# working.net
KiCad netlist of a schematic drawn in EAGLE
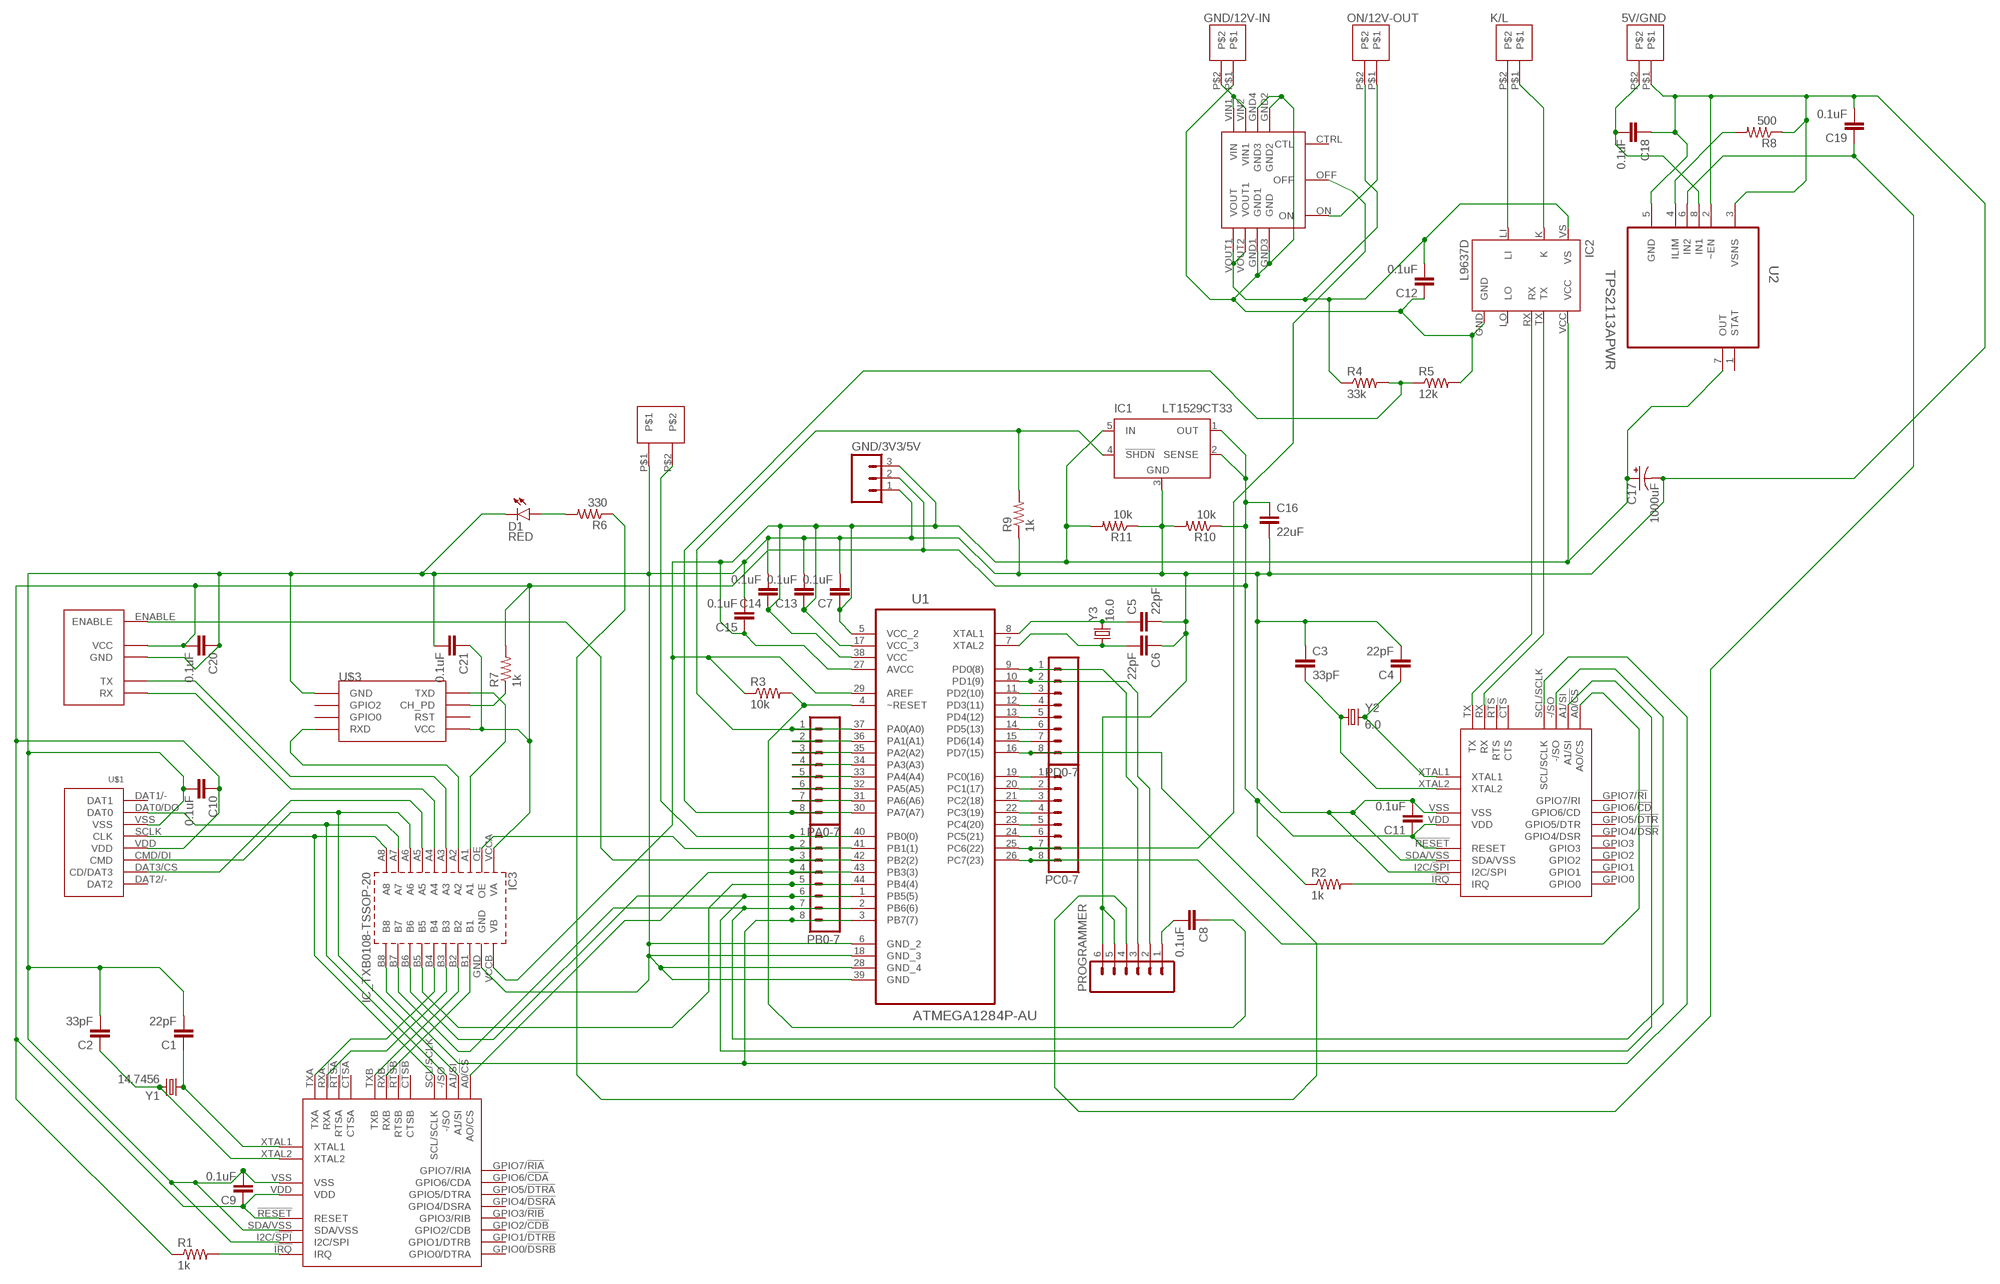
[diagram p0: schematic, sheet 1]

(export (version "E")
  (design (tool "Eeschema 10.0.6"))
  (components
    (comp (ref "5V/GND")
      (value "2-PIN-TERMINAL")
      (footprint "eagle-import:2-PIN-TERMINAL")
      (libsource (lib "eagle-import") (part "2-PIN-TERMINAL"))
    )
    (comp (ref "C1")
      (value "22pF")
      (footprint "eagle-import:0805")
      (libsource (lib "eagle-import") (part "SparkFun-Passives_CAP0805"))
    )
    (comp (ref "C2")
      (value "33pF")
      (footprint "eagle-import:0805")
      (libsource (lib "eagle-import") (part "SparkFun-Passives_CAP0805"))
    )
    (comp (ref "C3")
      (value "33pF")
      (footprint "eagle-import:0805")
      (libsource (lib "eagle-import") (part "SparkFun-Passives_CAP0805"))
    )
    (comp (ref "C4")
      (value "22pF")
      (footprint "eagle-import:0805")
      (libsource (lib "eagle-import") (part "SparkFun-Passives_CAP0805"))
    )
    (comp (ref "C5")
      (value "22pF")
      (footprint "eagle-import:0805")
      (libsource (lib "eagle-import") (part "SparkFun-Passives_CAP0805"))
    )
    (comp (ref "C6")
      (value "22pF")
      (footprint "eagle-import:0805")
      (libsource (lib "eagle-import") (part "SparkFun-Passives_CAP0805"))
    )
    (comp (ref "C7")
      (value "0.1uF")
      (footprint "eagle-import:0603-CAP")
      (libsource (lib "eagle-import") (part "CAP0603-CAP"))
    )
    (comp (ref "C8")
      (value "0.1uF")
      (footprint "eagle-import:0805")
      (libsource (lib "eagle-import") (part "SparkFun-Passives_CAP0805"))
    )
    (comp (ref "C9")
      (value "0.1uF")
      (footprint "eagle-import:0603-CAP")
      (libsource (lib "eagle-import") (part "CAP0603-CAP"))
    )
    (comp (ref "C10")
      (value "0.1uF")
      (footprint "eagle-import:0603-CAP")
      (libsource (lib "eagle-import") (part "CAP0603-CAP"))
    )
    (comp (ref "C11")
      (value "0.1uF")
      (footprint "eagle-import:0603-CAP")
      (libsource (lib "eagle-import") (part "CAP0603-CAP"))
    )
    (comp (ref "C12")
      (value "0.1uF")
      (footprint "eagle-import:0603-CAP")
      (libsource (lib "eagle-import") (part "CAP0603-CAP"))
    )
    (comp (ref "C13")
      (value "0.1uF")
      (footprint "eagle-import:0603-CAP")
      (libsource (lib "eagle-import") (part "CAP0603-CAP"))
    )
    (comp (ref "C14")
      (value "0.1uF")
      (footprint "eagle-import:0603-CAP")
      (libsource (lib "eagle-import") (part "CAP0603-CAP"))
    )
    (comp (ref "C15")
      (value "0.1uF")
      (footprint "eagle-import:0603-CAP")
      (libsource (lib "eagle-import") (part "CAP0603-CAP"))
    )
    (comp (ref "C16")
      (value "22uF")
      (footprint "eagle-import:1206")
      (libsource (lib "eagle-import") (part "CAP1206"))
    )
    (comp (ref "C17")
      (value "1000uF")
      (footprint "eagle-import:PANASONIC_G")
      (libsource (lib "eagle-import") (part "CPOL-USG"))
    )
    (comp (ref "C18")
      (value "0.1uF")
      (footprint "eagle-import:0603-CAP")
      (libsource (lib "eagle-import") (part "CAP0603-CAP"))
    )
    (comp (ref "C19")
      (value "0.1uF")
      (footprint "eagle-import:0603-CAP")
      (libsource (lib "eagle-import") (part "CAP0603-CAP"))
    )
    (comp (ref "C20")
      (value "0.1uF")
      (footprint "eagle-import:0603-CAP")
      (libsource (lib "eagle-import") (part "CAP0603-CAP"))
    )
    (comp (ref "C21")
      (value "0.1uF")
      (footprint "eagle-import:0603-CAP")
      (libsource (lib "eagle-import") (part "CAP0603-CAP"))
    )
    (comp (ref "D1")
      (value "RED")
      (footprint "eagle-import:LED5MM")
      (libsource (lib "eagle-import") (part "LED5MM"))
    )
    (comp (ref "GND/3V3/5V")
      (value "M03PTH")
      (footprint "eagle-import:1X03")
      (libsource (lib "eagle-import") (part "M03PTH"))
    )
    (comp (ref "GND/12V-IN")
      (value "2-PIN-TERMINAL")
      (footprint "eagle-import:2-PIN-TERMINAL")
      (libsource (lib "eagle-import") (part "2-PIN-TERMINAL"))
    )
    (comp (ref "IC1")
      (value "LT1529CT33")
      (footprint "eagle-import:TO220-5")
      (libsource (lib "eagle-import") (part "LT1529T"))
    )
    (comp (ref "IC2")
      (value "L9637D")
      (footprint "eagle-import:SO08")
      (libsource (lib "eagle-import") (part "L9637D"))
    )
    (comp (ref "IC3")
      (value "IC_TXB0108-TSSOP-20")
      (footprint "eagle-import:TSSOP-20")
      (libsource (lib "eagle-import") (part "IC_TXB0108-TSSOP-20"))
    )
    (comp (ref "K/L")
      (value "2-PIN-TERMINAL")
      (footprint "eagle-import:2-PIN-TERMINAL")
      (libsource (lib "eagle-import") (part "2-PIN-TERMINAL"))
    )
    (comp (ref "ON/12V-OUT")
      (value "2-PIN-TERMINAL")
      (footprint "eagle-import:2-PIN-TERMINAL")
      (libsource (lib "eagle-import") (part "2-PIN-TERMINAL"))
    )
    (comp (ref "PA0-7")
      (value "M08")
      (footprint "eagle-import:1X08_ROUND")
      (libsource (lib "eagle-import") (part "M08"))
    )
    (comp (ref "PB0-7")
      (value "M08")
      (footprint "eagle-import:1X08_ROUND")
      (libsource (lib "eagle-import") (part "M08"))
    )
    (comp (ref "PC0-7")
      (value "M08")
      (footprint "eagle-import:1X08_ROUND")
      (libsource (lib "eagle-import") (part "M08"))
    )
    (comp (ref "PD0-7")
      (value "M08")
      (footprint "eagle-import:1X08_ROUND")
      (libsource (lib "eagle-import") (part "M08"))
    )
    (comp (ref "PROGRAMMER")
      (value "M06SILK_FEMALE_PTH")
      (footprint "eagle-import:1X06")
      (libsource (lib "eagle-import") (part "M06SILK_FEMALE_PTH"))
    )
    (comp (ref "R1")
      (value "1k")
      (footprint "eagle-import:0805")
      (libsource (lib "eagle-import") (part "RESISTOR0805-RES"))
    )
    (comp (ref "R2")
      (value "1k")
      (footprint "eagle-import:0805")
      (libsource (lib "eagle-import") (part "RESISTOR0805-RES"))
    )
    (comp (ref "R3")
      (value "10k")
      (footprint "eagle-import:0805")
      (libsource (lib "eagle-import") (part "RESISTOR0805-RES"))
    )
    (comp (ref "R4")
      (value "33k")
      (footprint "eagle-import:0805")
      (libsource (lib "eagle-import") (part "RESISTOR0805-RES"))
    )
    (comp (ref "R5")
      (value "12k")
      (footprint "eagle-import:0805")
      (libsource (lib "eagle-import") (part "RESISTOR0805-RES"))
    )
    (comp (ref "R6")
      (value "330")
      (footprint "eagle-import:0805")
      (libsource (lib "eagle-import") (part "RESISTOR0805-RES"))
    )
    (comp (ref "R7")
      (value "1k")
      (footprint "eagle-import:0805")
      (libsource (lib "eagle-import") (part "RESISTOR0805-RES"))
    )
    (comp (ref "R8")
      (value "500")
      (footprint "eagle-import:0805")
      (libsource (lib "eagle-import") (part "RESISTOR0805-RES"))
    )
    (comp (ref "R9")
      (value "1k")
      (footprint "eagle-import:0805")
      (libsource (lib "eagle-import") (part "RESISTOR0805-RES"))
    )
    (comp (ref "R10")
      (value "10k")
      (footprint "eagle-import:0805")
      (libsource (lib "eagle-import") (part "RESISTOR0805-RES"))
    )
    (comp (ref "R11")
      (value "10k")
      (footprint "eagle-import:0805")
      (libsource (lib "eagle-import") (part "RESISTOR0805-RES"))
    )
    (comp (ref "U$1")
      (value "CON_MICROSDHINGED")
      (footprint "eagle-import:CON_MICROSD_HINGED")
      (libsource (lib "eagle-import") (part "CON_MICROSDHINGED"))
    )
    (comp (ref "U$2")
      (value "SC16IS752IPW")
      (footprint "eagle-import:TSSOP28")
      (libsource (lib "eagle-import") (part "SC16IS752IPW"))
    )
    (comp (ref "U$3")
      (value "ESP01")
      (footprint "eagle-import:ESP01")
      (libsource (lib "eagle-import") (part "ESP01"))
    )
    (comp (ref "U$4")
      (value "MINI")
      (footprint "eagle-import:MINI")
      (libsource (lib "eagle-import") (part "MINI"))
    )
    (comp (ref "U$5")
      (value "FEATHERWING")
      (footprint "eagle-import:FEATHERWING")
      (libsource (lib "eagle-import") (part "FEATHERWING"))
    )
    (comp (ref "U$7")
      (value "SC16IS750IPW")
      (footprint "eagle-import:TSSOP-24")
      (libsource (lib "eagle-import") (part "SC16IS750IPW"))
    )
    (comp (ref "U$11")
      (value "PIEZO")
      (footprint "eagle-import:17MM-PIEZO")
      (libsource (lib "eagle-import") (part "PIEZO"))
    )
    (comp (ref "U1")
      (value "ATMEGA1284P-AU")
      (footprint "eagle-import:QFP80P1200X1200X120-44N")
      (libsource (lib "eagle-import") (part "ATMEGA1284P-AU"))
    )
    (comp (ref "U2")
      (value "TPS2113APWR")
      (footprint "eagle-import:SOP65P640X120-8N")
      (libsource (lib "eagle-import") (part "TPS2113APWR"))
    )
    (comp (ref "Y1")
      (value "14.7456")
      (footprint "eagle-import:HC49US")
      (libsource (lib "eagle-import") (part "CRYSTALHC49US"))
    )
    (comp (ref "Y2")
      (value "6.0")
      (footprint "eagle-import:HC49US")
      (libsource (lib "eagle-import") (part "CRYSTALHC49US"))
    )
    (comp (ref "Y3")
      (value "16.0")
      (footprint "eagle-import:HC49US")
      (libsource (lib "eagle-import") (part "CRYSTALHC49US"))
    )
  )
  (nets
    (net (code "1") (name "Net-(C1-Pad1)") (class "Default")
      (node (ref "C1") (pin "1") (pinfunction "1_1") (pintype "passive"))
      (node (ref "U$2") (pin "XTAL1") (pinfunction "XTAL1_XTAL1") (pintype "bidirectional"))
      (node (ref "Y1") (pin "1") (pinfunction "1_1") (pintype "passive"))
    )
    (net (code "2") (name "Net-(C2-Pad1)") (class "Default")
      (node (ref "C2") (pin "1") (pinfunction "1_1") (pintype "passive"))
      (node (ref "U$2") (pin "XTAL2") (pinfunction "XTAL2_XTAL2") (pintype "bidirectional"))
      (node (ref "Y1") (pin "2") (pinfunction "2_2") (pintype "passive"))
    )
    (net (code "3") (name "Net-(C3-Pad2)") (class "Default")
      (node (ref "C3") (pin "2") (pinfunction "2_2") (pintype "passive"))
      (node (ref "U$7") (pin "XTAL2") (pinfunction "XTAL2_XTAL2") (pintype "bidirectional"))
      (node (ref "Y2") (pin "1") (pinfunction "1_1") (pintype "passive"))
    )
    (net (code "4") (name "Net-(C4-Pad1)") (class "Default")
      (node (ref "C4") (pin "1") (pinfunction "1_1") (pintype "passive"))
      (node (ref "U$7") (pin "XTAL1") (pinfunction "XTAL1_XTAL1") (pintype "bidirectional"))
      (node (ref "Y2") (pin "2") (pinfunction "2_2") (pintype "passive"))
    )
    (net (code "5") (name "Net-(C8-Pad2)") (class "Default")
      (node (ref "C8") (pin "2") (pinfunction "2_2") (pintype "passive"))
      (node (ref "PROGRAMMER") (pin "1") (pinfunction "1_1") (pintype "passive"))
    )
    (net (code "6") (name "Net-(D1-C)") (class "Default")
      (node (ref "5V/GND") (pin "P$1") (pinfunction "P$1_P$1") (pintype "bidirectional"))
      (node (ref "C1") (pin "2") (pinfunction "2_2") (pintype "passive"))
      (node (ref "C10") (pin "2") (pinfunction "2_2") (pintype "passive"))
      (node (ref "C11") (pin "2") (pinfunction "2_2") (pintype "passive"))
      (node (ref "C13") (pin "2") (pinfunction "2_2") (pintype "passive"))
      (node (ref "C14") (pin "2") (pinfunction "2_2") (pintype "passive"))
      (node (ref "C15") (pin "2") (pinfunction "2_2") (pintype "passive"))
      (node (ref "C16") (pin "2") (pinfunction "2_2") (pintype "passive"))
      (node (ref "C17") (pin "-") (pinfunction "-_-") (pintype "passive"))
      (node (ref "C18") (pin "1") (pinfunction "1_1") (pintype "passive"))
      (node (ref "C19") (pin "2") (pinfunction "2_2") (pintype "passive"))
      (node (ref "C2") (pin "2") (pinfunction "2_2") (pintype "passive"))
      (node (ref "C20") (pin "1") (pinfunction "1_1") (pintype "passive"))
      (node (ref "C21") (pin "2") (pinfunction "2_2") (pintype "passive"))
      (node (ref "C3") (pin "1") (pinfunction "1_1") (pintype "passive"))
      (node (ref "C4") (pin "2") (pinfunction "2_2") (pintype "passive"))
      (node (ref "C5") (pin "2") (pinfunction "2_2") (pintype "passive"))
      (node (ref "C6") (pin "1") (pinfunction "1_1") (pintype "passive"))
      (node (ref "C7") (pin "2") (pinfunction "2_2") (pintype "passive"))
      (node (ref "C9") (pin "2") (pinfunction "2_2") (pintype "passive"))
      (node (ref "D1") (pin "K") (pinfunction "C_K") (pintype "passive"))
      (node (ref "GND/3V3/5V") (pin "1") (pinfunction "1_1") (pintype "passive"))
      (node (ref "IC1") (pin "3") (pinfunction "GND_3") (pintype "power_in"))
      (node (ref "IC3") (pin "GND") (pinfunction "GND_GND") (pintype "bidirectional"))
      (node (ref "PROGRAMMER") (pin "5") (pinfunction "5_5") (pintype "passive"))
      (node (ref "PROGRAMMER") (pin "6") (pinfunction "6_6") (pintype "passive"))
      (node (ref "R10") (pin "2") (pinfunction "2_2") (pintype "passive"))
      (node (ref "R11") (pin "1") (pinfunction "1_1") (pintype "passive"))
      (node (ref "R8") (pin "1") (pinfunction "1_1") (pintype "passive"))
      (node (ref "R9") (pin "1") (pinfunction "1_1") (pintype "passive"))
      (node (ref "U$1") (pin "VSS") (pinfunction "VSS_VSS") (pintype "bidirectional"))
      (node (ref "U$11") (pin "P$1") (pinfunction "P$1_P$1") (pintype "bidirectional"))
      (node (ref "U$2") (pin "I2C/!SPI") (pinfunction "I2C/SPI_I2C/!SPI") (pintype "bidirectional"))
      (node (ref "U$2") (pin "SDA/VSS") (pinfunction "SDA/VSS_SDA/VSS") (pintype "bidirectional"))
      (node (ref "U$2") (pin "VSS") (pinfunction "VSS_VSS") (pintype "bidirectional"))
      (node (ref "U$3") (pin "GND") (pinfunction "GND_GND") (pintype "bidirectional"))
      (node (ref "U$5") (pin "GND") (pinfunction "GND_GND") (pintype "bidirectional"))
      (node (ref "U$7") (pin "I2C/!SPI") (pinfunction "I2C/SPI_I2C/!SPI") (pintype "bidirectional"))
      (node (ref "U$7") (pin "SDA/VSS") (pinfunction "SDA/VSS_SDA/VSS") (pintype "bidirectional"))
      (node (ref "U$7") (pin "VSS") (pinfunction "VSS_VSS") (pintype "bidirectional"))
      (node (ref "U1") (pin "18") (pinfunction "GND_3_18") (pintype "passive"))
      (node (ref "U1") (pin "28") (pinfunction "GND_4_28") (pintype "passive"))
      (node (ref "U1") (pin "39") (pinfunction "GND_39") (pintype "passive"))
      (node (ref "U1") (pin "6") (pinfunction "GND_2_6") (pintype "passive"))
      (node (ref "U2") (pin "2") (pinfunction "~{EN}_2") (pintype "input"))
      (node (ref "U2") (pin "3") (pinfunction "VSNS_3") (pintype "power_in"))
      (node (ref "U2") (pin "5") (pinfunction "GND_5") (pintype "passive"))
    )
    (net (code "7") (name "Net-(D1-PadA)") (class "Default")
      (node (ref "D1") (pin "A") (pinfunction "A_A") (pintype "passive"))
      (node (ref "R6") (pin "2") (pinfunction "2_2") (pintype "passive"))
    )
    (net (code "8") (name "Net-(IC1-IN)") (class "Default")
      (node (ref "C13") (pin "1") (pinfunction "1_1") (pintype "passive"))
      (node (ref "C14") (pin "1") (pinfunction "1_1") (pintype "passive"))
      (node (ref "C15") (pin "1") (pinfunction "1_1") (pintype "passive"))
      (node (ref "C17") (pin "+") (pinfunction "+_+") (pintype "passive"))
      (node (ref "C7") (pin "1") (pinfunction "1_1") (pintype "passive"))
      (node (ref "GND/3V3/5V") (pin "3") (pinfunction "3_3") (pintype "passive"))
      (node (ref "IC1") (pin "5") (pinfunction "IN_5") (pintype "input"))
      (node (ref "IC2") (pin "VCC") (pinfunction "VCC_VCC") (pintype "power_in"))
      (node (ref "IC3") (pin "VCCB") (pinfunction "VB_VCCB") (pintype "bidirectional"))
      (node (ref "R11") (pin "2") (pinfunction "2_2") (pintype "passive"))
      (node (ref "R3") (pin "1") (pinfunction "1_1") (pintype "passive"))
      (node (ref "U1") (pin "17") (pinfunction "VCC_3_17") (pintype "power_in"))
      (node (ref "U1") (pin "27") (pinfunction "AVCC_27") (pintype "power_in"))
      (node (ref "U1") (pin "29") (pinfunction "AREF_29") (pintype "input"))
      (node (ref "U1") (pin "38") (pinfunction "VCC_38") (pintype "power_in"))
      (node (ref "U1") (pin "5") (pinfunction "VCC_2_5") (pintype "power_in"))
      (node (ref "U2") (pin "7") (pinfunction "OUT_7") (pintype "output"))
    )
    (net (code "9") (name "Net-(IC1-OUT)") (class "Default")
      (node (ref "C10") (pin "1") (pinfunction "1_1") (pintype "passive"))
      (node (ref "C11") (pin "1") (pinfunction "1_1") (pintype "passive"))
      (node (ref "C16") (pin "1") (pinfunction "1_1") (pintype "passive"))
      (node (ref "C20") (pin "2") (pinfunction "2_2") (pintype "passive"))
      (node (ref "C21") (pin "1") (pinfunction "1_1") (pintype "passive"))
      (node (ref "C9") (pin "1") (pinfunction "1_1") (pintype "passive"))
      (node (ref "GND/3V3/5V") (pin "2") (pinfunction "2_2") (pintype "passive"))
      (node (ref "IC1") (pin "1") (pinfunction "OUT_1") (pintype "output"))
      (node (ref "IC1") (pin "2") (pinfunction "SENSE_2") (pintype "input"))
      (node (ref "IC3") (pin "VCCA") (pinfunction "VA_VCCA") (pintype "bidirectional"))
      (node (ref "R1") (pin "1") (pinfunction "1_1") (pintype "passive"))
      (node (ref "R10") (pin "1") (pinfunction "1_1") (pintype "passive"))
      (node (ref "R2") (pin "1") (pinfunction "1_1") (pintype "passive"))
      (node (ref "R7") (pin "2") (pinfunction "2_2") (pintype "passive"))
      (node (ref "U$1") (pin "VDD") (pinfunction "VDD_VDD") (pintype "bidirectional"))
      (node (ref "U$2") (pin "!RESET") (pinfunction "RESET_!RESET") (pintype "bidirectional"))
      (node (ref "U$2") (pin "VDD") (pinfunction "VDD_VDD") (pintype "bidirectional"))
      (node (ref "U$3") (pin "VCC") (pinfunction "VCC_VCC") (pintype "bidirectional"))
      (node (ref "U$5") (pin "VCC") (pinfunction "VCC_VCC") (pintype "bidirectional"))
      (node (ref "U$7") (pin "!RESET") (pinfunction "RESET_!RESET") (pintype "bidirectional"))
      (node (ref "U$7") (pin "VDD") (pinfunction "VDD_VDD") (pintype "bidirectional"))
    )
    (net (code "10") (name "Net-(IC1-~{SHDN})") (class "Default")
      (node (ref "IC1") (pin "4") (pinfunction "~{SHDN}_4") (pintype "input"))
      (node (ref "PA0-7") (pin "1") (pinfunction "1_1") (pintype "passive"))
      (node (ref "R9") (pin "2") (pinfunction "2_2") (pintype "passive"))
      (node (ref "U1") (pin "37") (pinfunction "PA0(A0)_37") (pintype "bidirectional"))
    )
    (net (code "11") (name "Net-(IC2-PadK)") (class "Default")
      (node (ref "IC2") (pin "K") (pinfunction "K_K") (pintype "input"))
      (node (ref "K/L") (pin "P$1") (pinfunction "P$1_P$1") (pintype "bidirectional"))
    )
    (net (code "12") (name "Net-(IC2-PadLI)") (class "Default")
      (node (ref "IC2") (pin "LI") (pinfunction "LI_LI") (pintype "input"))
      (node (ref "K/L") (pin "P$2") (pinfunction "P$2_P$2") (pintype "bidirectional"))
    )
    (net (code "13") (name "Net-(IC2-PadRX)") (class "Default")
      (node (ref "IC2") (pin "RX") (pinfunction "RX_RX") (pintype "output"))
      (node (ref "U$7") (pin "TX") (pinfunction "TX_TX") (pintype "bidirectional"))
    )
    (net (code "14") (name "Net-(IC2-PadTX)") (class "Default")
      (node (ref "IC2") (pin "TX") (pinfunction "TX_TX") (pintype "input"))
      (node (ref "U$7") (pin "RX") (pinfunction "RX_RX") (pintype "bidirectional"))
    )
    (net (code "15") (name "Net-(IC3-PadB1)") (class "Default")
      (node (ref "IC3") (pin "B1") (pinfunction "B1_B1") (pintype "bidirectional"))
      (node (ref "U$2") (pin "RXB") (pinfunction "RXB_RXB") (pintype "bidirectional"))
    )
    (net (code "16") (name "Net-(IC3-PadB2)") (class "Default")
      (node (ref "IC3") (pin "B2") (pinfunction "B2_B2") (pintype "bidirectional"))
      (node (ref "U$2") (pin "TXB") (pinfunction "TXB_TXB") (pintype "bidirectional"))
    )
    (net (code "17") (name "Net-(IC3-PadB3)") (class "Default")
      (node (ref "IC3") (pin "B3") (pinfunction "B3_B3") (pintype "bidirectional"))
      (node (ref "U$2") (pin "RXA") (pinfunction "RXA_RXA") (pintype "bidirectional"))
    )
    (net (code "18") (name "Net-(IC3-PadB4)") (class "Default")
      (node (ref "IC3") (pin "B4") (pinfunction "B4_B4") (pintype "bidirectional"))
      (node (ref "U$2") (pin "TXA") (pinfunction "TXA_TXA") (pintype "bidirectional"))
    )
    (net (code "19") (name "Net-(ON/12V-OUT-PadP$1)") (class "Default")
      (node (ref "ON/12V-OUT") (pin "P$1") (pinfunction "P$1_P$1") (pintype "bidirectional"))
      (node (ref "U$4") (pin "ON") (pinfunction "ON_ON") (pintype "bidirectional"))
    )
    (net (code "20") (name "Net-(R7-Pad1)") (class "Default")
      (node (ref "R7") (pin "1") (pinfunction "1_1") (pintype "passive"))
      (node (ref "U$3") (pin "CH_PD") (pinfunction "CH_PD_CH_PD") (pintype "bidirectional"))
    )
    (net (code "21") (name "Net-(U$1-CD{slash}DAT3)") (class "Default")
      (node (ref "IC3") (pin "A5") (pinfunction "A5_A5") (pintype "bidirectional"))
      (node (ref "U$1") (pin "DAT3/CS") (pinfunction "CD/DAT3_DAT3/CS") (pintype "bidirectional"))
    )
    (net (code "22") (name "Net-(U$1-CLK)") (class "Default")
      (node (ref "IC3") (pin "A8") (pinfunction "A8_A8") (pintype "bidirectional"))
      (node (ref "U$1") (pin "SCLK") (pinfunction "CLK_SCLK") (pintype "bidirectional"))
      (node (ref "U$2") (pin "SCL/SCLK") (pinfunction "SCL/SCLK_SCL/SCLK") (pintype "bidirectional"))
    )
    (net (code "23") (name "Net-(U$1-CMD)") (class "Default")
      (node (ref "IC3") (pin "A6") (pinfunction "A6_A6") (pintype "bidirectional"))
      (node (ref "U$1") (pin "CMD/DI") (pinfunction "CMD_CMD/DI") (pintype "bidirectional"))
      (node (ref "U$2") (pin "A1/SI") (pinfunction "A1/SI_A1/SI") (pintype "bidirectional"))
    )
    (net (code "24") (name "Net-(U$1-DAT0)") (class "Default")
      (node (ref "IC3") (pin "A7") (pinfunction "A7_A7") (pintype "bidirectional"))
      (node (ref "U$1") (pin "DAT0/DO") (pinfunction "DAT0_DAT0/DO") (pintype "bidirectional"))
      (node (ref "U$2") (pin "-/SO") (pinfunction "-/SO_-/SO") (pintype "bidirectional"))
    )
    (net (code "25") (name "Net-(U$2-AO{slash}CS)") (class "Default")
      (node (ref "PB0-7") (pin "4") (pinfunction "4_4") (pintype "passive"))
      (node (ref "U$2") (pin "A0/!CS") (pinfunction "AO/CS_A0/!CS") (pintype "bidirectional"))
      (node (ref "U1") (pin "43") (pinfunction "PB3(3)_43") (pintype "bidirectional"))
    )
    (net (code "26") (name "Net-(U$2-IRQ)") (class "Default")
      (node (ref "R1") (pin "2") (pinfunction "2_2") (pintype "passive"))
      (node (ref "U$2") (pin "!IRQ") (pinfunction "IRQ_!IRQ") (pintype "bidirectional"))
    )
    (net (code "27") (name "Net-(U$3-RXD)") (class "Default")
      (node (ref "IC3") (pin "A2") (pinfunction "A2_A2") (pintype "bidirectional"))
      (node (ref "U$3") (pin "RX") (pinfunction "RXD_RX") (pintype "bidirectional"))
    )
    (net (code "28") (name "Net-(U$3-TXD)") (class "Default")
      (node (ref "IC3") (pin "A1") (pinfunction "A1_A1") (pintype "bidirectional"))
      (node (ref "U$3") (pin "TX") (pinfunction "TXD_TX") (pintype "bidirectional"))
    )
    (net (code "29") (name "Net-(U$4-GND)") (class "Default")
      (node (ref "C12") (pin "1") (pinfunction "1_1") (pintype "passive"))
      (node (ref "GND/12V-IN") (pin "P$1") (pinfunction "P$1_P$1") (pintype "bidirectional"))
      (node (ref "IC2") (pin "GND") (pinfunction "GND_GND") (pintype "power_in"))
      (node (ref "R5") (pin "2") (pinfunction "2_2") (pintype "passive"))
      (node (ref "U$4") (pin "GND1") (pinfunction "GND1_GND1") (pintype "bidirectional"))
      (node (ref "U$4") (pin "GND2") (pinfunction "GND2_GND2") (pintype "bidirectional"))
      (node (ref "U$4") (pin "GND3") (pinfunction "GND_GND3") (pintype "bidirectional"))
      (node (ref "U$4") (pin "GND4") (pinfunction "GND3_GND4") (pintype "bidirectional"))
    )
    (net (code "30") (name "Net-(U$4-VIN)") (class "Default")
      (node (ref "GND/12V-IN") (pin "P$2") (pinfunction "P$2_P$2") (pintype "bidirectional"))
      (node (ref "U$4") (pin "VIN1") (pinfunction "VIN_VIN1") (pintype "bidirectional"))
      (node (ref "U$4") (pin "VIN2") (pinfunction "VIN1_VIN2") (pintype "bidirectional"))
    )
    (net (code "31") (name "Net-(U$4-VOUT)") (class "Default")
      (node (ref "C12") (pin "2") (pinfunction "2_2") (pintype "passive"))
      (node (ref "IC2") (pin "VS") (pinfunction "VS_VS") (pintype "power_in"))
      (node (ref "ON/12V-OUT") (pin "P$2") (pinfunction "P$2_P$2") (pintype "bidirectional"))
      (node (ref "R4") (pin "1") (pinfunction "1_1") (pintype "passive"))
      (node (ref "U$4") (pin "VOUT1") (pinfunction "VOUT_VOUT1") (pintype "bidirectional"))
      (node (ref "U$4") (pin "VOUT2") (pinfunction "VOUT1_VOUT2") (pintype "bidirectional"))
    )
    (net (code "32") (name "Net-(U$5-RX)") (class "Default")
      (node (ref "IC3") (pin "A4") (pinfunction "A4_A4") (pintype "bidirectional"))
      (node (ref "U$5") (pin "RX-2") (pinfunction "RX_RX-2") (pintype "bidirectional"))
    )
    (net (code "33") (name "Net-(U$5-TX)") (class "Default")
      (node (ref "IC3") (pin "A3") (pinfunction "A3_A3") (pintype "bidirectional"))
      (node (ref "U$5") (pin "TX-2") (pinfunction "TX_TX-2") (pintype "bidirectional"))
    )
    (net (code "34") (name "Net-(U$7-AO{slash}CS)") (class "Default")
      (node (ref "PC0-7") (pin "8") (pinfunction "8_8") (pintype "passive"))
      (node (ref "U$7") (pin "A0/!CS") (pinfunction "AO/CS_A0/!CS") (pintype "bidirectional"))
      (node (ref "U1") (pin "26") (pinfunction "PC7(23)_26") (pintype "bidirectional"))
    )
    (net (code "35") (name "Net-(U$7-IRQ)") (class "Default")
      (node (ref "R2") (pin "2") (pinfunction "2_2") (pintype "passive"))
      (node (ref "U$7") (pin "!IRQ") (pinfunction "IRQ_!IRQ") (pintype "bidirectional"))
    )
    (net (code "36") (name "Net-(U1-PA1(A1))") (class "Default")
      (node (ref "PA0-7") (pin "2") (pinfunction "2_2") (pintype "passive"))
      (node (ref "U1") (pin "36") (pinfunction "PA1(A1)_36") (pintype "bidirectional"))
    )
    (net (code "37") (name "Net-(U1-PA2(A2))") (class "Default")
      (node (ref "PA0-7") (pin "3") (pinfunction "3_3") (pintype "passive"))
      (node (ref "U1") (pin "35") (pinfunction "PA2(A2)_35") (pintype "bidirectional"))
    )
    (net (code "38") (name "Net-(U1-PA3(A3))") (class "Default")
      (node (ref "PA0-7") (pin "4") (pinfunction "4_4") (pintype "passive"))
      (node (ref "U1") (pin "34") (pinfunction "PA3(A3)_34") (pintype "bidirectional"))
    )
    (net (code "39") (name "Net-(U1-PA4(A4))") (class "Default")
      (node (ref "PA0-7") (pin "5") (pinfunction "5_5") (pintype "passive"))
      (node (ref "U1") (pin "33") (pinfunction "PA4(A4)_33") (pintype "bidirectional"))
    )
    (net (code "40") (name "Net-(U1-PA5(A5))") (class "Default")
      (node (ref "PA0-7") (pin "6") (pinfunction "6_6") (pintype "passive"))
      (node (ref "U1") (pin "32") (pinfunction "PA5(A5)_32") (pintype "bidirectional"))
    )
    (net (code "41") (name "Net-(U1-PA6(A6))") (class "Default")
      (node (ref "PA0-7") (pin "7") (pinfunction "7_7") (pintype "passive"))
      (node (ref "U1") (pin "31") (pinfunction "PA6(A6)_31") (pintype "bidirectional"))
    )
    (net (code "42") (name "Net-(U1-PA7(A7))") (class "Default")
      (node (ref "PA0-7") (pin "8") (pinfunction "8_8") (pintype "passive"))
      (node (ref "R4") (pin "2") (pinfunction "2_2") (pintype "passive"))
      (node (ref "R5") (pin "1") (pinfunction "1_1") (pintype "passive"))
      (node (ref "U1") (pin "30") (pinfunction "PA7(A7)_30") (pintype "bidirectional"))
    )
    (net (code "43") (name "Net-(U1-PB0(0))") (class "Default")
      (node (ref "PB0-7") (pin "1") (pinfunction "1_1") (pintype "passive"))
      (node (ref "U$11") (pin "P$2") (pinfunction "P$2_P$2") (pintype "bidirectional"))
      (node (ref "U1") (pin "40") (pinfunction "PB0(0)_40") (pintype "bidirectional"))
    )
    (net (code "44") (name "Net-(U1-PB1(1))") (class "Default")
      (node (ref "IC3") (pin "OE") (pinfunction "OE_OE") (pintype "bidirectional"))
      (node (ref "PB0-7") (pin "2") (pinfunction "2_2") (pintype "passive"))
      (node (ref "U1") (pin "41") (pinfunction "PB1(1)_41") (pintype "bidirectional"))
    )
    (net (code "45") (name "Net-(U1-PB2(2))") (class "Default")
      (node (ref "PB0-7") (pin "3") (pinfunction "3_3") (pintype "passive"))
      (node (ref "U$5") (pin "ENABLE") (pinfunction "ENABLE_ENABLE") (pintype "bidirectional"))
      (node (ref "U1") (pin "42") (pinfunction "PB2(2)_42") (pintype "bidirectional"))
    )
    (net (code "46") (name "Net-(U1-PB4(4))") (class "Default")
      (node (ref "IC3") (pin "B5") (pinfunction "B5_B5") (pintype "bidirectional"))
      (node (ref "PB0-7") (pin "5") (pinfunction "5_5") (pintype "passive"))
      (node (ref "U1") (pin "44") (pinfunction "PB4(4)_44") (pintype "bidirectional"))
    )
    (net (code "47") (name "Net-(U1-PB5(5))") (class "Default")
      (node (ref "IC3") (pin "B6") (pinfunction "B6_B6") (pintype "bidirectional"))
      (node (ref "PB0-7") (pin "6") (pinfunction "6_6") (pintype "passive"))
      (node (ref "U$7") (pin "A1/SI") (pinfunction "A1/SI_A1/SI") (pintype "bidirectional"))
      (node (ref "U1") (pin "1") (pinfunction "PB5(5)_1") (pintype "bidirectional"))
    )
    (net (code "48") (name "Net-(U1-PB6(6))") (class "Default")
      (node (ref "IC3") (pin "B7") (pinfunction "B7_B7") (pintype "bidirectional"))
      (node (ref "PB0-7") (pin "7") (pinfunction "7_7") (pintype "passive"))
      (node (ref "U$7") (pin "-/SO") (pinfunction "-/SO_-/SO") (pintype "bidirectional"))
      (node (ref "U1") (pin "2") (pinfunction "PB6(6)_2") (pintype "bidirectional"))
    )
    (net (code "49") (name "Net-(U1-PB7(7))") (class "Default")
      (node (ref "IC3") (pin "B8") (pinfunction "B8_B8") (pintype "bidirectional"))
      (node (ref "PB0-7") (pin "8") (pinfunction "8_8") (pintype "passive"))
      (node (ref "U$7") (pin "SCL/SCLK") (pinfunction "SCL/SCLK_SCL/SCLK") (pintype "bidirectional"))
      (node (ref "U1") (pin "3") (pinfunction "PB7(7)_3") (pintype "bidirectional"))
    )
    (net (code "50") (name "Net-(U1-PC0(16))") (class "Default")
      (node (ref "PC0-7") (pin "1") (pinfunction "1_1") (pintype "passive"))
      (node (ref "U1") (pin "19") (pinfunction "PC0(16)_19") (pintype "bidirectional"))
    )
    (net (code "51") (name "Net-(U1-PC1(17))") (class "Default")
      (node (ref "PC0-7") (pin "2") (pinfunction "2_2") (pintype "passive"))
      (node (ref "U1") (pin "20") (pinfunction "PC1(17)_20") (pintype "bidirectional"))
    )
    (net (code "52") (name "Net-(U1-PC2(18))") (class "Default")
      (node (ref "PC0-7") (pin "3") (pinfunction "3_3") (pintype "passive"))
      (node (ref "U1") (pin "21") (pinfunction "PC2(18)_21") (pintype "bidirectional"))
    )
    (net (code "53") (name "Net-(U1-PC3(19))") (class "Default")
      (node (ref "PC0-7") (pin "4") (pinfunction "4_4") (pintype "passive"))
      (node (ref "U1") (pin "22") (pinfunction "PC3(19)_22") (pintype "bidirectional"))
    )
    (net (code "54") (name "Net-(U1-PC4(20))") (class "Default")
      (node (ref "PC0-7") (pin "5") (pinfunction "5_5") (pintype "passive"))
      (node (ref "U1") (pin "23") (pinfunction "PC4(20)_23") (pintype "bidirectional"))
    )
    (net (code "55") (name "Net-(U1-PC5(21))") (class "Default")
      (node (ref "PC0-7") (pin "6") (pinfunction "6_6") (pintype "passive"))
      (node (ref "U1") (pin "24") (pinfunction "PC5(21)_24") (pintype "bidirectional"))
    )
    (net (code "56") (name "Net-(U1-PC6(22))") (class "Default")
      (node (ref "PC0-7") (pin "7") (pinfunction "7_7") (pintype "passive"))
      (node (ref "U$4") (pin "OFF") (pinfunction "OFF_OFF") (pintype "bidirectional"))
      (node (ref "U1") (pin "25") (pinfunction "PC6(22)_25") (pintype "bidirectional"))
    )
    (net (code "57") (name "Net-(U1-PD0(8))") (class "Default")
      (node (ref "PD0-7") (pin "1") (pinfunction "1_1") (pintype "passive"))
      (node (ref "PROGRAMMER") (pin "3") (pinfunction "3_3") (pintype "passive"))
      (node (ref "U1") (pin "9") (pinfunction "PD0(8)_9") (pintype "bidirectional"))
    )
    (net (code "58") (name "Net-(U1-PD1(9))") (class "Default")
      (node (ref "PD0-7") (pin "2") (pinfunction "2_2") (pintype "passive"))
      (node (ref "PROGRAMMER") (pin "2") (pinfunction "2_2") (pintype "passive"))
      (node (ref "U1") (pin "10") (pinfunction "PD1(9)_10") (pintype "bidirectional"))
    )
    (net (code "59") (name "Net-(U1-PD2(10))") (class "Default")
      (node (ref "PD0-7") (pin "3") (pinfunction "3_3") (pintype "passive"))
      (node (ref "U1") (pin "11") (pinfunction "PD2(10)_11") (pintype "bidirectional"))
    )
    (net (code "60") (name "Net-(U1-PD3(11))") (class "Default")
      (node (ref "PD0-7") (pin "4") (pinfunction "4_4") (pintype "passive"))
      (node (ref "U1") (pin "12") (pinfunction "PD3(11)_12") (pintype "bidirectional"))
    )
    (net (code "61") (name "Net-(U1-PD4(12))") (class "Default")
      (node (ref "PD0-7") (pin "5") (pinfunction "5_5") (pintype "passive"))
      (node (ref "U1") (pin "13") (pinfunction "PD4(12)_13") (pintype "bidirectional"))
    )
    (net (code "62") (name "Net-(U1-PD5(13))") (class "Default")
      (node (ref "PD0-7") (pin "6") (pinfunction "6_6") (pintype "passive"))
      (node (ref "U1") (pin "14") (pinfunction "PD5(13)_14") (pintype "bidirectional"))
    )
    (net (code "63") (name "Net-(U1-PD6(14))") (class "Default")
      (node (ref "PD0-7") (pin "7") (pinfunction "7_7") (pintype "passive"))
      (node (ref "U1") (pin "15") (pinfunction "PD6(14)_15") (pintype "bidirectional"))
    )
    (net (code "64") (name "Net-(U1-PD7(15))") (class "Default")
      (node (ref "PD0-7") (pin "8") (pinfunction "8_8") (pintype "passive"))
      (node (ref "R6") (pin "1") (pinfunction "1_1") (pintype "passive"))
      (node (ref "U1") (pin "16") (pinfunction "PD7(15)_16") (pintype "bidirectional"))
    )
    (net (code "65") (name "Net-(U1-XTAL1)") (class "Default")
      (node (ref "C5") (pin "1") (pinfunction "1_1") (pintype "passive"))
      (node (ref "U1") (pin "8") (pinfunction "XTAL1_8") (pintype "input"))
      (node (ref "Y3") (pin "2") (pinfunction "2_2") (pintype "passive"))
    )
    (net (code "66") (name "Net-(U1-XTAL2)") (class "Default")
      (node (ref "C6") (pin "2") (pinfunction "2_2") (pintype "passive"))
      (node (ref "U1") (pin "7") (pinfunction "XTAL2_7") (pintype "output"))
      (node (ref "Y3") (pin "1") (pinfunction "1_1") (pintype "passive"))
    )
    (net (code "67") (name "Net-(U1-~{RESET})") (class "Default")
      (node (ref "C8") (pin "1") (pinfunction "1_1") (pintype "passive"))
      (node (ref "R3") (pin "2") (pinfunction "2_2") (pintype "passive"))
      (node (ref "U1") (pin "4") (pinfunction "~{RESET}_4") (pintype "input"))
    )
    (net (code "68") (name "Net-(U2-ILIM)") (class "Default")
      (node (ref "R8") (pin "2") (pinfunction "2_2") (pintype "passive"))
      (node (ref "U2") (pin "4") (pinfunction "ILIM_4") (pintype "input"))
    )
    (net (code "69") (name "Net-(U2-IN1)") (class "Default")
      (node (ref "5V/GND") (pin "P$2") (pinfunction "P$2_P$2") (pintype "bidirectional"))
      (node (ref "C18") (pin "2") (pinfunction "2_2") (pintype "passive"))
      (node (ref "U2") (pin "8") (pinfunction "IN1_8") (pintype "input"))
    )
    (net (code "70") (name "Net-(U2-IN2)") (class "Default")
      (node (ref "C19") (pin "1") (pinfunction "1_1") (pintype "passive"))
      (node (ref "PROGRAMMER") (pin "4") (pinfunction "4_4") (pintype "passive"))
      (node (ref "U2") (pin "6") (pinfunction "IN2_6") (pintype "input"))
    )
    (net (code "71") (name "unconnected-(IC2-PadLO)") (class "Default")
      (node (ref "IC2") (pin "LO") (pinfunction "LO_LO") (pintype "output"))
    )
    (net (code "72") (name "unconnected-(U$1-DAT1-PadDAT1{slash}-)") (class "Default")
      (node (ref "U$1") (pin "DAT1/-") (pinfunction "DAT1_DAT1/-") (pintype "bidirectional"))
    )
    (net (code "73") (name "unconnected-(U$1-DAT2-PadDAT2{slash}-)") (class "Default")
      (node (ref "U$1") (pin "DAT2/-") (pinfunction "DAT2_DAT2/-") (pintype "bidirectional"))
    )
    (net (code "74") (name "unconnected-(U$2-CTSA-Pad!CTSA)") (class "Default")
      (node (ref "U$2") (pin "!CTSA") (pinfunction "CTSA_!CTSA") (pintype "bidirectional"))
    )
    (net (code "75") (name "unconnected-(U$2-CTSB-Pad!CTSB)") (class "Default")
      (node (ref "U$2") (pin "!CTSB") (pinfunction "CTSB_!CTSB") (pintype "bidirectional"))
    )
    (net (code "76") (name "unconnected-(U$2-GPIO0{slash}DTRA-PadGPIO0{slash}!DSRB)") (class "Default")
      (node (ref "U$2") (pin "GPIO0/!DSRB") (pinfunction "GPIO0/DTRA_GPIO0/!DSRB") (pintype "bidirectional"))
    )
    (net (code "77") (name "unconnected-(U$2-GPIO1{slash}DTRB-PadGPIO1{slash}!DTRB)") (class "Default")
      (node (ref "U$2") (pin "GPIO1/!DTRB") (pinfunction "GPIO1/DTRB_GPIO1/!DTRB") (pintype "bidirectional"))
    )
    (net (code "78") (name "unconnected-(U$2-GPIO2{slash}CDB-PadGPIO2{slash}!CDB)") (class "Default")
      (node (ref "U$2") (pin "GPIO2/!CDB") (pinfunction "GPIO2/CDB_GPIO2/!CDB") (pintype "bidirectional"))
    )
    (net (code "79") (name "unconnected-(U$2-GPIO3{slash}RIB-PadGPIO3{slash}!RIB)") (class "Default")
      (node (ref "U$2") (pin "GPIO3/!RIB") (pinfunction "GPIO3/RIB_GPIO3/!RIB") (pintype "bidirectional"))
    )
    (net (code "80") (name "unconnected-(U$2-GPIO4{slash}DSRA-PadGPIO4{slash}!DSRA)") (class "Default")
      (node (ref "U$2") (pin "GPIO4/!DSRA") (pinfunction "GPIO4/DSRA_GPIO4/!DSRA") (pintype "bidirectional"))
    )
    (net (code "81") (name "unconnected-(U$2-GPIO5{slash}DTRA-PadGPIO5{slash}!DTRA)") (class "Default")
      (node (ref "U$2") (pin "GPIO5/!DTRA") (pinfunction "GPIO5/DTRA_GPIO5/!DTRA") (pintype "bidirectional"))
    )
    (net (code "82") (name "unconnected-(U$2-GPIO6{slash}CDA-PadGPIO6{slash}!CDA)") (class "Default")
      (node (ref "U$2") (pin "GPIO6/!CDA") (pinfunction "GPIO6/CDA_GPIO6/!CDA") (pintype "bidirectional"))
    )
    (net (code "83") (name "unconnected-(U$2-GPIO7{slash}RIA-PadGPIO7{slash}!RIA)") (class "Default")
      (node (ref "U$2") (pin "GPIO7/!RIA") (pinfunction "GPIO7/RIA_GPIO7/!RIA") (pintype "bidirectional"))
    )
    (net (code "84") (name "unconnected-(U$2-RTSA-Pad!RTSA)") (class "Default")
      (node (ref "U$2") (pin "!RTSA") (pinfunction "RTSA_!RTSA") (pintype "bidirectional"))
    )
    (net (code "85") (name "unconnected-(U$2-RTSB-Pad!RTSB)") (class "Default")
      (node (ref "U$2") (pin "!RTSB") (pinfunction "RTSB_!RTSB") (pintype "bidirectional"))
    )
    (net (code "86") (name "unconnected-(U$3-PadGPIO0)") (class "Default")
      (node (ref "U$3") (pin "GPIO0") (pinfunction "GPIO0_GPIO0") (pintype "bidirectional"))
    )
    (net (code "87") (name "unconnected-(U$3-PadGPIO2)") (class "Default")
      (node (ref "U$3") (pin "GPIO2") (pinfunction "GPIO2_GPIO2") (pintype "bidirectional"))
    )
    (net (code "88") (name "unconnected-(U$3-PadRST)") (class "Default")
      (node (ref "U$3") (pin "RST") (pinfunction "RST_RST") (pintype "bidirectional"))
    )
    (net (code "89") (name "unconnected-(U$4-CTL-PadCTRL)") (class "Default")
      (node (ref "U$4") (pin "CTRL") (pinfunction "CTL_CTRL") (pintype "bidirectional"))
    )
    (net (code "90") (name "unconnected-(U$7-CTS-Pad!CTS)") (class "Default")
      (node (ref "U$7") (pin "!CTS") (pinfunction "CTS_!CTS") (pintype "bidirectional"))
    )
    (net (code "91") (name "unconnected-(U$7-GPIO4{slash}DSR-PadGPIO4{slash}!DSR)") (class "Default")
      (node (ref "U$7") (pin "GPIO4/!DSR") (pinfunction "GPIO4/DSR_GPIO4/!DSR") (pintype "bidirectional"))
    )
    (net (code "92") (name "unconnected-(U$7-GPIO5{slash}DTR-PadGPIO5{slash}!DTR)") (class "Default")
      (node (ref "U$7") (pin "GPIO5/!DTR") (pinfunction "GPIO5/DTR_GPIO5/!DTR") (pintype "bidirectional"))
    )
    (net (code "93") (name "unconnected-(U$7-GPIO6{slash}CD-PadGPIO6{slash}!CD)") (class "Default")
      (node (ref "U$7") (pin "GPIO6/!CD") (pinfunction "GPIO6/CD_GPIO6/!CD") (pintype "bidirectional"))
    )
    (net (code "94") (name "unconnected-(U$7-GPIO7{slash}RI-PadGPIO7{slash}!RI)") (class "Default")
      (node (ref "U$7") (pin "GPIO7/!RI") (pinfunction "GPIO7/RI_GPIO7/!RI") (pintype "bidirectional"))
    )
    (net (code "95") (name "unconnected-(U$7-PadGPIO0)") (class "Default")
      (node (ref "U$7") (pin "GPIO0") (pinfunction "GPIO0_GPIO0") (pintype "bidirectional"))
    )
    (net (code "96") (name "unconnected-(U$7-PadGPIO1)") (class "Default")
      (node (ref "U$7") (pin "GPIO1") (pinfunction "GPIO1_GPIO1") (pintype "bidirectional"))
    )
    (net (code "97") (name "unconnected-(U$7-PadGPIO2)") (class "Default")
      (node (ref "U$7") (pin "GPIO2") (pinfunction "GPIO2_GPIO2") (pintype "bidirectional"))
    )
    (net (code "98") (name "unconnected-(U$7-PadGPIO3)") (class "Default")
      (node (ref "U$7") (pin "GPIO3") (pinfunction "GPIO3_GPIO3") (pintype "bidirectional"))
    )
    (net (code "99") (name "unconnected-(U$7-RTS-Pad!RTS)") (class "Default")
      (node (ref "U$7") (pin "!RTS") (pinfunction "RTS_!RTS") (pintype "bidirectional"))
    )
    (net (code "100") (name "unconnected-(U2-STAT-Pad1)") (class "Default")
      (node (ref "U2") (pin "1") (pinfunction "STAT_1") (pintype "output"))
    )
  )
)
